# SENSORS.net
KiCad netlist of a schematic drawn in Altium Designer
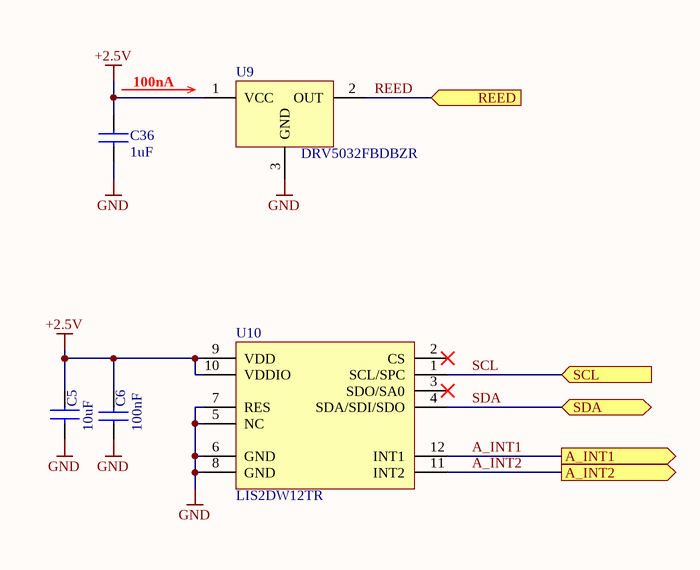
[diagram p0: SENSORS.SchDoc]

(export (version "E")
  (design (tool "Eeschema 10.0.6"))
  (components
    (comp (ref "C5")
      (value "10uF")
      (footprint "CAP0603")
      (description "Cap Ceramic 10uF 10V X5R 10% SMD 0603 85C Paper T/R")
      (fields
        (field (name "MANUFACTURER") "Samsung")
        (field (name "MANUFACTURER PART NUMBER") "CL10A106KP8NNNC")
      )
      (libsource (lib "Passive") (part "C - 10uF/10V"))
    )
    (comp (ref "C6")
      (value "100nF")
      (footprint "CAP0402")
      (description "0.1 F, 16 V,  5%, X5R, MC Series")
      (fields
        (field (name "MANUFACTURER") "Multicomp")
        (field (name "MANUFACTURER PART NUMBER") "MC0402X104J160CT")
      )
      (libsource (lib "Passive") (part "C - 100nF/0402"))
    )
    (comp (ref "C36")
      (value "1uF")
      (footprint "CAP0402")
      (description "CAP CER 1UF 10V 20% X5R 0402")
      (fields
        (field (name "MANUFACTURER") "Murata")
        (field (name "MANUFACTURER PART NUMBER") "GRM155R61A105ME15D")
      )
      (libsource (lib "Passive") (part "C - 1uF/0402"))
    )
    (comp (ref "U9")
      (value "DRV5032FBDBZR")
      (footprint "SOT23-3AL")
      (description "Board Mount Hall Effect/Magnetic Sensors LP HALL 32FBDBZR")
      (fields
        (field (name "MANUFACTURER") "TDK InvenSense")
        (field (name "MANUFACTURER PART NUMBER") "MPU-9250")
      )
      (libsource (lib "Active") (part "SEN - DRV5032FBDBZR"))
    )
    (comp (ref "U10")
      (value "LIS2DW12TR")
      (footprint "LGA-12")
      (description "MEMS Accelerometer, Digital, X, Y, Z, ± 2g, ± 4g, ± 8g, ± 16g, 1.62 V, 3.6 V")
      (fields
        (field (name "MANUFACTURER") "TDK InvenSense")
        (field (name "MANUFACTURER PART NUMBER") "MPU-9250")
      )
      (libsource (lib "Active") (part "SEN - LIS2DW12TR"))
    )
  )
  (nets
    (net (code "1") (name "+2.5V") (class "Default")
      (node (ref "C36") (pin "1") (pinfunction "1_1") (pintype "passive"))
      (node (ref "C5") (pin "1") (pinfunction "1_1") (pintype "passive"))
      (node (ref "C6") (pin "2") (pinfunction "2_2") (pintype "passive"))
      (node (ref "U10") (pin "10") (pinfunction "VDDIO_10") (pintype "passive"))
      (node (ref "U10") (pin "9") (pinfunction "VDD_9") (pintype "passive"))
      (node (ref "U9") (pin "1") (pinfunction "VCC_1") (pintype "passive"))
    )
    (net (code "2") (name "/A_INT1") (class "Default")
      (node (ref "U10") (pin "12") (pinfunction "INT1_12") (pintype "passive"))
    )
    (net (code "3") (name "/A_INT2") (class "Default")
      (node (ref "U10") (pin "11") (pinfunction "INT2_11") (pintype "passive"))
    )
    (net (code "4") (name "/REED") (class "Default")
      (node (ref "U9") (pin "2") (pinfunction "OUT_2") (pintype "passive"))
    )
    (net (code "5") (name "/SCL") (class "Default")
      (node (ref "U10") (pin "1") (pinfunction "SCL/SPC_1") (pintype "passive"))
    )
    (net (code "6") (name "/SDA") (class "Default")
      (node (ref "U10") (pin "4") (pinfunction "SDA/SDI/SDO_4") (pintype "passive"))
    )
    (net (code "7") (name "GND") (class "Default")
      (node (ref "C36") (pin "2") (pinfunction "2_2") (pintype "passive"))
      (node (ref "C5") (pin "2") (pinfunction "2_2") (pintype "passive"))
      (node (ref "C6") (pin "1") (pinfunction "1_1") (pintype "passive"))
      (node (ref "U10") (pin "5") (pinfunction "NC_5") (pintype "passive"))
      (node (ref "U10") (pin "6") (pinfunction "GND_6") (pintype "passive"))
      (node (ref "U10") (pin "7") (pinfunction "RES_7") (pintype "passive"))
      (node (ref "U10") (pin "8") (pinfunction "GND_8") (pintype "passive"))
      (node (ref "U9") (pin "3") (pinfunction "GND_3") (pintype "passive"))
    )
    (net (code "8") (name "unconnected-(U10-CS-Pad2)") (class "Default")
      (node (ref "U10") (pin "2") (pinfunction "CS_2") (pintype "passive+no_connect"))
    )
    (net (code "9") (name "unconnected-(U10-SDO{slash}SA0-Pad3)") (class "Default")
      (node (ref "U10") (pin "3") (pinfunction "SDO/SA0_3") (pintype "passive+no_connect"))
    )
  )
)
